# -Z_Panel_FM_Ver3.net
KiCad netlist of a schematic drawn in EAGLE
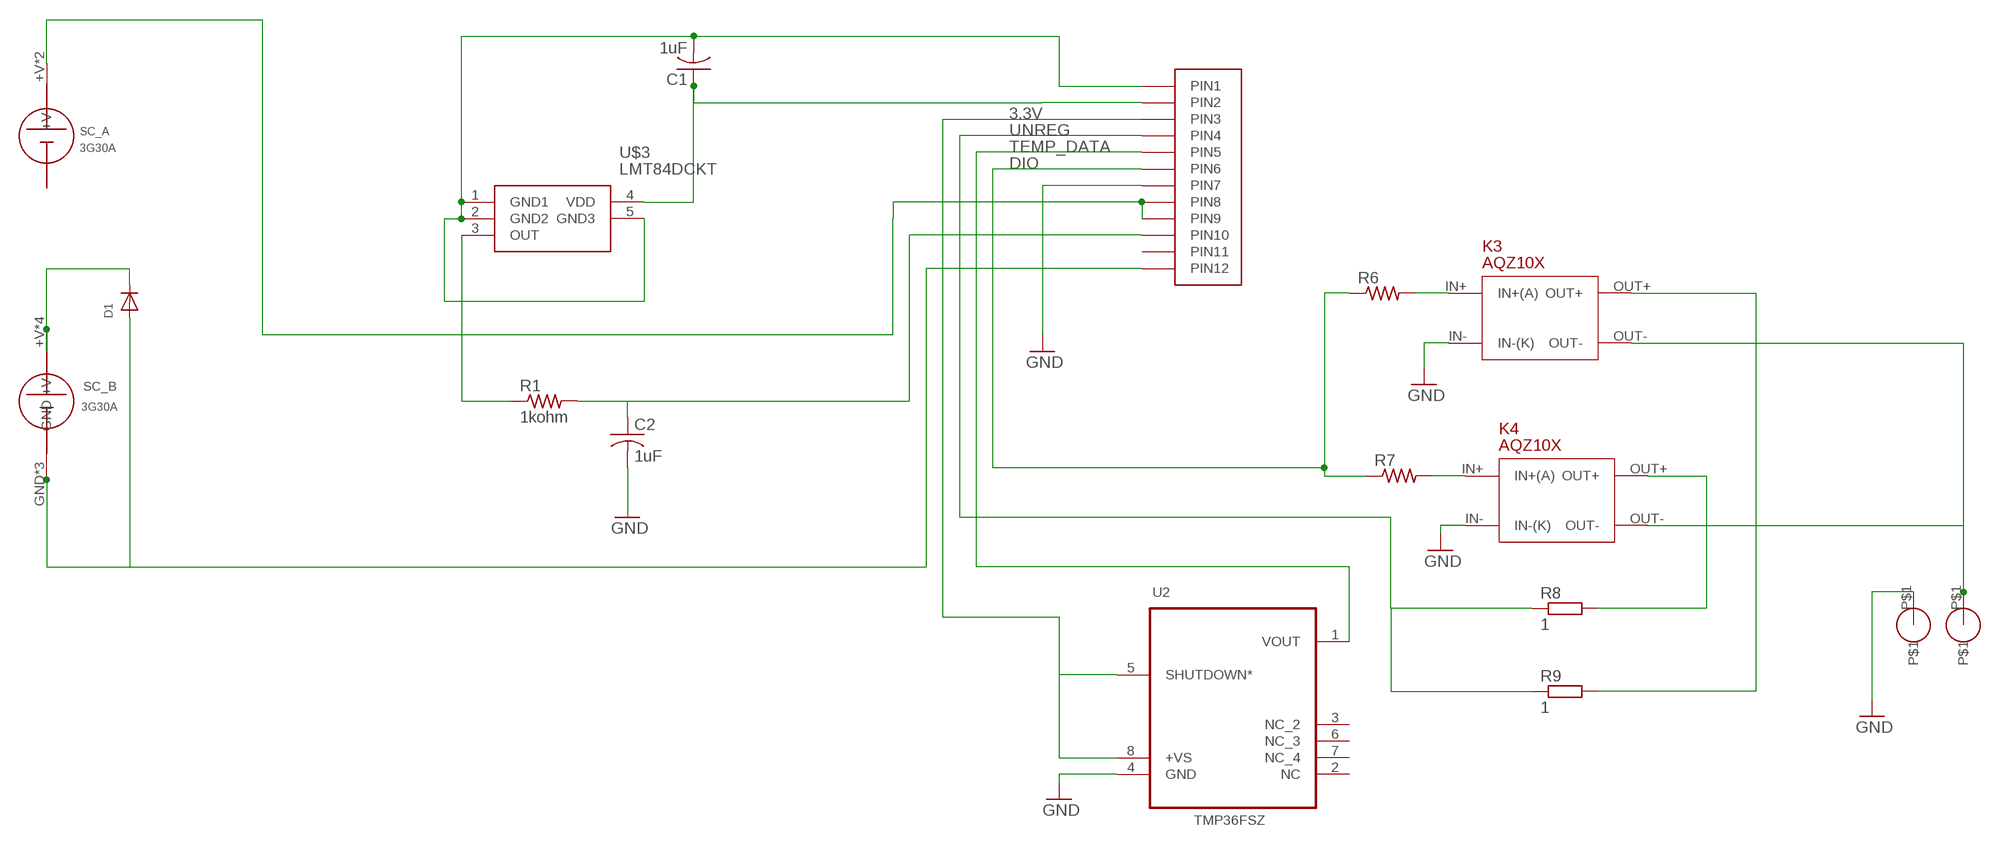
[diagram p0: schematic, sheet 1]

(export (version "E")
  (design (tool "Eeschema 10.0.6"))
  (components
    (comp (ref "C1")
      (value "1uF")
      (footprint "eagle-import:C0805")
      (libsource (lib "eagle-import") (part "C-USC0805"))
    )
    (comp (ref "C2")
      (value "1uF")
      (footprint "eagle-import:C0805")
      (libsource (lib "eagle-import") (part "C-USC0805"))
    )
    (comp (ref "D1")
      (value "DIODE_SOD-123FL")
      (footprint "eagle-import:SOD-123FL")
      (libsource (lib "eagle-import") (part "DIODE_SOD-123FL"))
    )
    (comp (ref "GND9")
      (value "NICR_HOLE")
      (footprint "eagle-import:NICR_HOLE")
      (libsource (lib "eagle-import") (part "NICR_HOLE"))
    )
    (comp (ref "HOLE1")
      (value "NICR_HOLE")
      (footprint "eagle-import:NICR_HOLE")
      (libsource (lib "eagle-import") (part "NICR_HOLE"))
    )
    (comp (ref "K3")
      (value "AQZ10X")
      (footprint "eagle-import:AQZ10X")
      (libsource (lib "eagle-import") (part "AQZ10X"))
    )
    (comp (ref "K4")
      (value "AQZ10X")
      (footprint "eagle-import:AQZ10X")
      (libsource (lib "eagle-import") (part "AQZ10X"))
    )
    (comp (ref "R1")
      (value "1kohm")
      (footprint "eagle-import:R0402")
      (libsource (lib "eagle-import") (part "R-US_R0402"))
    )
    (comp (ref "R6")
      (value "R-US_R0402")
      (footprint "eagle-import:R0402")
      (libsource (lib "eagle-import") (part "adafruit_ufl_R-US_R0402"))
    )
    (comp (ref "R7")
      (value "R-US_R0402")
      (footprint "eagle-import:R0402")
      (libsource (lib "eagle-import") (part "adafruit_ufl_R-US_R0402"))
    )
    (comp (ref "R8")
      (value "1")
      (footprint "eagle-import:R1218")
      (libsource (lib "eagle-import") (part "R-EU_R1218"))
    )
    (comp (ref "R9")
      (value "1")
      (footprint "eagle-import:R1218")
      (libsource (lib "eagle-import") (part "R-EU_R1218"))
    )
    (comp (ref "U$1")
      (value "HEADER12PIN")
      (footprint "eagle-import:HEADER12PIN")
      (libsource (lib "eagle-import") (part "HEADER12PIN"))
    )
    (comp (ref "U$3")
      (value "LMT84DCKT")
      (footprint "eagle-import:SOT65P210X110-5N")
      (fields (field (name "RS_PART_NUMBER") "8115860"))
      (libsource (lib "eagle-import") (part "LMT84DCKT"))
    )
    (comp (ref "U$4")
      (value "SC_A")
      (footprint "eagle-import:SC_A")
      (libsource (lib "eagle-import") (part "SC_A"))
    )
    (comp (ref "U$5")
      (value "SC_B")
      (footprint "eagle-import:SC_B")
      (libsource (lib "eagle-import") (part "SC_B"))
    )
    (comp (ref "U2")
      (value "TMP36FSZ")
      (footprint "eagle-import:SOIC_N")
      (libsource (lib "eagle-import") (part "TMP36FSZ"))
    )
  )
  (nets
    (net (code "1") (name "/3.3V") (class "Default")
      (node (ref "U$1") (pin "P3") (pinfunction "PIN3_P3") (pintype "bidirectional"))
      (node (ref "U2") (pin "5") (pinfunction "SHUTDOWN*_5") (pintype "passive"))
      (node (ref "U2") (pin "8") (pinfunction "+VS_8") (pintype "power_in"))
    )
    (net (code "2") (name "/DIO") (class "Default")
      (node (ref "R6") (pin "1") (pinfunction "1_1") (pintype "passive"))
      (node (ref "R7") (pin "1") (pinfunction "1_1") (pintype "passive"))
      (node (ref "U$1") (pin "P6") (pinfunction "PIN6_P6") (pintype "bidirectional"))
    )
    (net (code "3") (name "/TEMP_DATA") (class "Default")
      (node (ref "U$1") (pin "P5") (pinfunction "PIN5_P5") (pintype "bidirectional"))
      (node (ref "U2") (pin "1") (pinfunction "VOUT_1") (pintype "passive"))
    )
    (net (code "4") (name "/UNREG") (class "Default")
      (node (ref "R8") (pin "1") (pinfunction "1_1") (pintype "passive"))
      (node (ref "R9") (pin "1") (pinfunction "1_1") (pintype "passive"))
      (node (ref "U$1") (pin "P4") (pinfunction "PIN4_P4") (pintype "bidirectional"))
    )
    (net (code "5") (name "GND") (class "Default")
      (node (ref "C1") (pin "2") (pinfunction "2_2") (pintype "passive"))
      (node (ref "C2") (pin "2") (pinfunction "2_2") (pintype "passive"))
      (node (ref "D1") (pin "A") (pinfunction "A_A") (pintype "passive"))
      (node (ref "GND9") (pin "P$1") (pinfunction "P$1_P$1") (pintype "bidirectional"))
      (node (ref "K3") (pin "IN-") (pinfunction "IN-(K)_IN-") (pintype "bidirectional"))
      (node (ref "K4") (pin "IN-") (pinfunction "IN-(K)_IN-") (pintype "bidirectional"))
      (node (ref "U$1") (pin "P1") (pinfunction "PIN1_P1") (pintype "bidirectional"))
      (node (ref "U$1") (pin "P12") (pinfunction "PIN12_P12") (pintype "bidirectional"))
      (node (ref "U$1") (pin "P7") (pinfunction "PIN7_P7") (pintype "bidirectional"))
      (node (ref "U$3") (pin "1") (pinfunction "GND1_1") (pintype "power_in"))
      (node (ref "U$3") (pin "2") (pinfunction "GND2_2") (pintype "power_in"))
      (node (ref "U$3") (pin "5") (pinfunction "GND3_5") (pintype "power_in"))
      (node (ref "U$5") (pin "GND") (pinfunction "GND_GND") (pintype "bidirectional"))
      (node (ref "U$5") (pin "GND1") (pinfunction "GND_GND1") (pintype "bidirectional"))
      (node (ref "U$5") (pin "GND2") (pinfunction "GND_GND2") (pintype "bidirectional"))
      (node (ref "U2") (pin "4") (pinfunction "GND_4") (pintype "passive"))
    )
    (net (code "6") (name "Net-(D1-PadC)") (class "Default")
      (node (ref "D1") (pin "C") (pinfunction "C_C") (pintype "passive"))
      (node (ref "U$5") (pin "+V") (pinfunction "+V_+V") (pintype "bidirectional"))
      (node (ref "U$5") (pin "+V2") (pinfunction "+V_+V2") (pintype "bidirectional"))
      (node (ref "U$5") (pin "+V3") (pinfunction "+V_+V3") (pintype "bidirectional"))
      (node (ref "U$5") (pin "+V4") (pinfunction "+V_+V4") (pintype "bidirectional"))
    )
    (net (code "7") (name "Net-(HOLE1-PadP$1)") (class "Default")
      (node (ref "HOLE1") (pin "P$1") (pinfunction "P$1_P$1") (pintype "bidirectional"))
      (node (ref "K3") (pin "OUT-") (pinfunction "OUT-_OUT-") (pintype "bidirectional"))
      (node (ref "K4") (pin "OUT-") (pinfunction "OUT-_OUT-") (pintype "bidirectional"))
    )
    (net (code "8") (name "Net-(K3-IN+(A))") (class "Default")
      (node (ref "K3") (pin "IN+") (pinfunction "IN+(A)_IN+") (pintype "bidirectional"))
      (node (ref "R6") (pin "2") (pinfunction "2_2") (pintype "passive"))
    )
    (net (code "9") (name "Net-(K3-PadOUT+)") (class "Default")
      (node (ref "K3") (pin "OUT+") (pinfunction "OUT+_OUT+") (pintype "bidirectional"))
      (node (ref "R9") (pin "2") (pinfunction "2_2") (pintype "passive"))
    )
    (net (code "10") (name "Net-(K4-IN+(A))") (class "Default")
      (node (ref "K4") (pin "IN+") (pinfunction "IN+(A)_IN+") (pintype "bidirectional"))
      (node (ref "R7") (pin "2") (pinfunction "2_2") (pintype "passive"))
    )
    (net (code "11") (name "Net-(K4-PadOUT+)") (class "Default")
      (node (ref "K4") (pin "OUT+") (pinfunction "OUT+_OUT+") (pintype "bidirectional"))
      (node (ref "R8") (pin "2") (pinfunction "2_2") (pintype "passive"))
    )
    (net (code "12") (name "Net-(U$1-PIN2)") (class "Default")
      (node (ref "C1") (pin "1") (pinfunction "1_1") (pintype "passive"))
      (node (ref "U$1") (pin "P2") (pinfunction "PIN2_P2") (pintype "bidirectional"))
      (node (ref "U$3") (pin "4") (pinfunction "VDD_4") (pintype "power_in"))
    )
    (net (code "13") (name "Net-(U$1-PIN8)") (class "Default")
      (node (ref "U$1") (pin "P8") (pinfunction "PIN8_P8") (pintype "bidirectional"))
      (node (ref "U$1") (pin "P9") (pinfunction "PIN9_P9") (pintype "bidirectional"))
      (node (ref "U$4") (pin "+V") (pinfunction "+V_+V") (pintype "bidirectional"))
      (node (ref "U$4") (pin "+V1") (pinfunction "+V_+V1") (pintype "bidirectional"))
    )
    (net (code "14") (name "Net-(U$1-PIN10)") (class "Default")
      (node (ref "C2") (pin "1") (pinfunction "1_1") (pintype "passive"))
      (node (ref "R1") (pin "2") (pinfunction "2_2") (pintype "passive"))
      (node (ref "U$1") (pin "P10") (pinfunction "PIN10_P10") (pintype "bidirectional"))
    )
    (net (code "15") (name "Net-(U$3-OUT)") (class "Default")
      (node (ref "R1") (pin "1") (pinfunction "1_1") (pintype "passive"))
      (node (ref "U$3") (pin "3") (pinfunction "OUT_3") (pintype "output"))
    )
    (net (code "16") (name "unconnected-(U$1-PIN11-PadP11)") (class "Default")
      (node (ref "U$1") (pin "P11") (pinfunction "PIN11_P11") (pintype "bidirectional"))
    )
    (net (code "17") (name "unconnected-(U2-NC-Pad2)") (class "Default")
      (node (ref "U2") (pin "2") (pinfunction "NC_2") (pintype "passive"))
    )
    (net (code "18") (name "unconnected-(U2-NC_2-Pad3)") (class "Default")
      (node (ref "U2") (pin "3") (pinfunction "NC_2_3") (pintype "passive"))
    )
    (net (code "19") (name "unconnected-(U2-NC_3-Pad6)") (class "Default")
      (node (ref "U2") (pin "6") (pinfunction "NC_3_6") (pintype "passive"))
    )
    (net (code "20") (name "unconnected-(U2-NC_4-Pad7)") (class "Default")
      (node (ref "U2") (pin "7") (pinfunction "NC_4_7") (pintype "passive"))
    )
  )
)
